# tree2023.net
KiCad netlist of a schematic drawn in EAGLE
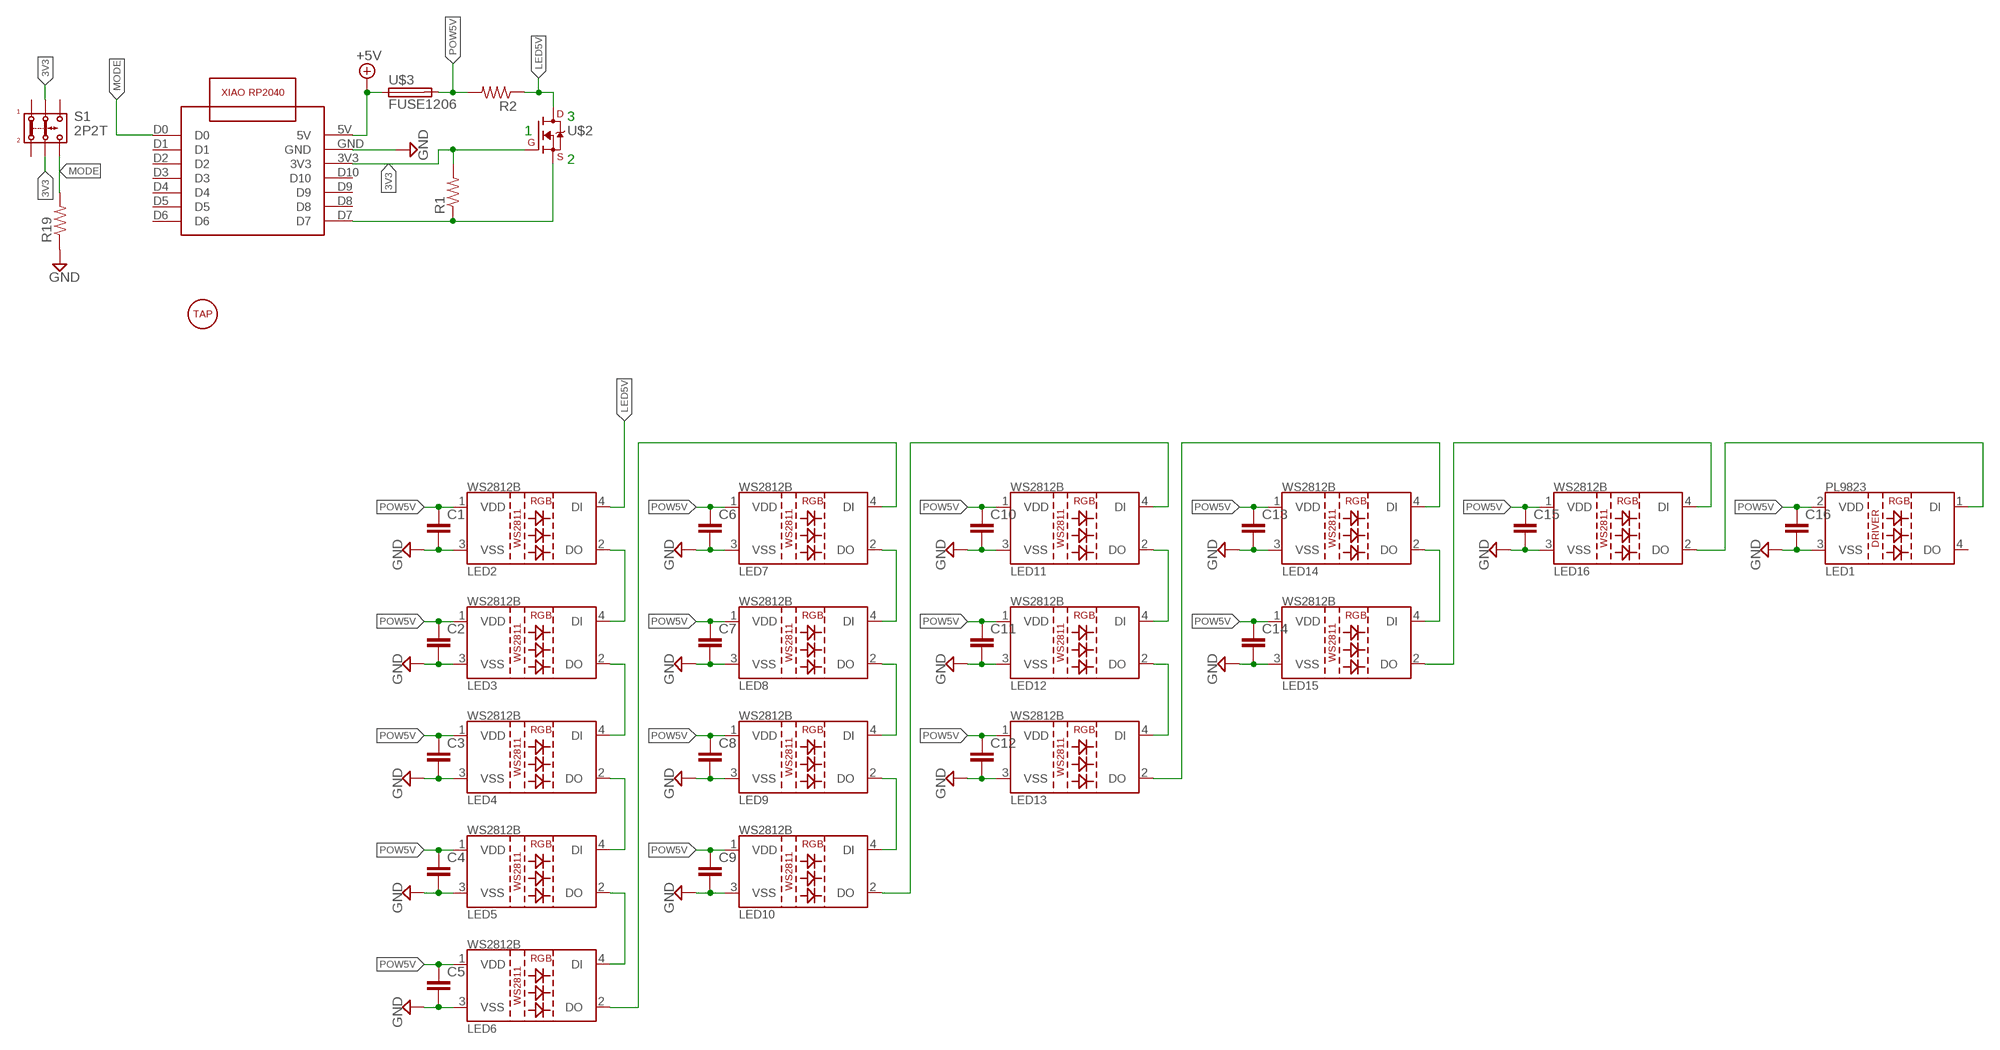
[diagram p0: schematic, sheet 1]

(export (version "E")
  (design (tool "Eeschema 10.0.6"))
  (components
    (comp (ref "C1")
      (value "C-EUC0805")
      (footprint "eagle-import:C0805")
      (libsource (lib "eagle-import") (part "C-EUC0805"))
    )
    (comp (ref "C2")
      (value "C-EUC0805")
      (footprint "eagle-import:C0805")
      (libsource (lib "eagle-import") (part "C-EUC0805"))
    )
    (comp (ref "C3")
      (value "C-EUC0805")
      (footprint "eagle-import:C0805")
      (libsource (lib "eagle-import") (part "C-EUC0805"))
    )
    (comp (ref "C4")
      (value "C-EUC0805")
      (footprint "eagle-import:C0805")
      (libsource (lib "eagle-import") (part "C-EUC0805"))
    )
    (comp (ref "C5")
      (value "C-EUC0805")
      (footprint "eagle-import:C0805")
      (libsource (lib "eagle-import") (part "C-EUC0805"))
    )
    (comp (ref "C6")
      (value "C-EUC0805")
      (footprint "eagle-import:C0805")
      (libsource (lib "eagle-import") (part "C-EUC0805"))
    )
    (comp (ref "C7")
      (value "C-EUC0805")
      (footprint "eagle-import:C0805")
      (libsource (lib "eagle-import") (part "C-EUC0805"))
    )
    (comp (ref "C8")
      (value "C-EUC0805")
      (footprint "eagle-import:C0805")
      (libsource (lib "eagle-import") (part "C-EUC0805"))
    )
    (comp (ref "C9")
      (value "C-EUC0805")
      (footprint "eagle-import:C0805")
      (libsource (lib "eagle-import") (part "C-EUC0805"))
    )
    (comp (ref "C10")
      (value "C-EUC0805")
      (footprint "eagle-import:C0805")
      (libsource (lib "eagle-import") (part "C-EUC0805"))
    )
    (comp (ref "C11")
      (value "C-EUC0805")
      (footprint "eagle-import:C0805")
      (libsource (lib "eagle-import") (part "C-EUC0805"))
    )
    (comp (ref "C12")
      (value "C-EUC0805")
      (footprint "eagle-import:C0805")
      (libsource (lib "eagle-import") (part "C-EUC0805"))
    )
    (comp (ref "C13")
      (value "C-EUC0805")
      (footprint "eagle-import:C0805")
      (libsource (lib "eagle-import") (part "C-EUC0805"))
    )
    (comp (ref "C14")
      (value "C-EUC0805")
      (footprint "eagle-import:C0805")
      (libsource (lib "eagle-import") (part "C-EUC0805"))
    )
    (comp (ref "C15")
      (value "C-EUC0805")
      (footprint "eagle-import:C0805")
      (libsource (lib "eagle-import") (part "C-EUC0805"))
    )
    (comp (ref "C16")
      (value "C-EUC0805")
      (footprint "eagle-import:C0805")
      (libsource (lib "eagle-import") (part "C-EUC0805"))
    )
    (comp (ref "LED1")
      (value "LED-PL9823-F5")
      (footprint "eagle-import:LED-PL9823-F5")
      (libsource (lib "eagle-import") (part "LED-PL9823-F5"))
    )
    (comp (ref "LED2")
      (value "LED-WS2812B")
      (footprint "eagle-import:LED-WS2812B")
      (libsource (lib "eagle-import") (part "LED-WS2812B"))
    )
    (comp (ref "LED3")
      (value "LED-WS2812B")
      (footprint "eagle-import:LED-WS2812B")
      (libsource (lib "eagle-import") (part "LED-WS2812B"))
    )
    (comp (ref "LED4")
      (value "LED-WS2812B")
      (footprint "eagle-import:LED-WS2812B")
      (libsource (lib "eagle-import") (part "LED-WS2812B"))
    )
    (comp (ref "LED5")
      (value "LED-WS2812B")
      (footprint "eagle-import:LED-WS2812B")
      (libsource (lib "eagle-import") (part "LED-WS2812B"))
    )
    (comp (ref "LED6")
      (value "LED-WS2812B")
      (footprint "eagle-import:LED-WS2812B")
      (libsource (lib "eagle-import") (part "LED-WS2812B"))
    )
    (comp (ref "LED7")
      (value "LED-WS2812B")
      (footprint "eagle-import:LED-WS2812B")
      (libsource (lib "eagle-import") (part "LED-WS2812B"))
    )
    (comp (ref "LED8")
      (value "LED-WS2812B")
      (footprint "eagle-import:LED-WS2812B")
      (libsource (lib "eagle-import") (part "LED-WS2812B"))
    )
    (comp (ref "LED9")
      (value "LED-WS2812B")
      (footprint "eagle-import:LED-WS2812B")
      (libsource (lib "eagle-import") (part "LED-WS2812B"))
    )
    (comp (ref "LED10")
      (value "LED-WS2812B")
      (footprint "eagle-import:LED-WS2812B")
      (libsource (lib "eagle-import") (part "LED-WS2812B"))
    )
    (comp (ref "LED11")
      (value "LED-WS2812B")
      (footprint "eagle-import:LED-WS2812B")
      (libsource (lib "eagle-import") (part "LED-WS2812B"))
    )
    (comp (ref "LED12")
      (value "LED-WS2812B")
      (footprint "eagle-import:LED-WS2812B")
      (libsource (lib "eagle-import") (part "LED-WS2812B"))
    )
    (comp (ref "LED13")
      (value "LED-WS2812B")
      (footprint "eagle-import:LED-WS2812B")
      (libsource (lib "eagle-import") (part "LED-WS2812B"))
    )
    (comp (ref "LED14")
      (value "LED-WS2812B")
      (footprint "eagle-import:LED-WS2812B")
      (libsource (lib "eagle-import") (part "LED-WS2812B"))
    )
    (comp (ref "LED15")
      (value "LED-WS2812B")
      (footprint "eagle-import:LED-WS2812B")
      (libsource (lib "eagle-import") (part "LED-WS2812B"))
    )
    (comp (ref "LED16")
      (value "LED-WS2812B")
      (footprint "eagle-import:LED-WS2812B")
      (libsource (lib "eagle-import") (part "LED-WS2812B"))
    )
    (comp (ref "R1")
      (value "R-US_R0603")
      (footprint "eagle-import:R0603")
      (libsource (lib "eagle-import") (part "R-US_R0603"))
    )
    (comp (ref "R2")
      (value "R-US_R0603")
      (footprint "eagle-import:R0603")
      (libsource (lib "eagle-import") (part "R-US_R0603"))
    )
    (comp (ref "R19")
      (value "R-US_R0603")
      (footprint "eagle-import:R0603")
      (libsource (lib "eagle-import") (part "R-US_R0603"))
    )
    (comp (ref "S1")
      (value "2P2T")
      (footprint "eagle-import:2P2T")
      (libsource (lib "eagle-import") (part "2P2T"))
    )
    (comp (ref "U$1")
      (value "XIAO-RP2040FRONT-SMD")
      (footprint "eagle-import:XIAO-RP2040-ASIDE-SMD")
      (libsource (lib "eagle-import") (part "XIAO-RP2040FRONT-SMD"))
    )
    (comp (ref "U$2")
      (value "IRML6344")
      (footprint "eagle-import:SOT23")
      (libsource (lib "eagle-import") (part "IRML6344"))
    )
    (comp (ref "U$3")
      (value "FUSE1206")
      (footprint "eagle-import:F1206")
      (libsource (lib "eagle-import") (part "FUSE1206"))
    )
    (comp (ref "U$4")
      (value "TAPHOLE3MM")
      (footprint "eagle-import:TAPHOLE-3MM")
      (libsource (lib "eagle-import") (part "TAPHOLE3MM"))
    )
  )
  (nets
    (net (code "1") (name "+5V") (class "Default")
      (node (ref "U$1") (pin "5V") (pinfunction "5V_5V") (pintype "bidirectional"))
      (node (ref "U$3") (pin "1") (pinfunction "1_1") (pintype "passive"))
    )
    (net (code "2") (name "3V3") (class "Default")
      (node (ref "R1") (pin "2") (pinfunction "2_2") (pintype "passive"))
      (node (ref "S1") (pin "2.1") (pinfunction "2.1_2.1") (pintype "passive"))
      (node (ref "S1") (pin "2.2") (pinfunction "2.2_2.2") (pintype "passive"))
      (node (ref "U$1") (pin "3V3") (pinfunction "3V3_3V3") (pintype "bidirectional"))
      (node (ref "U$2") (pin "1") (pinfunction "G_1") (pintype "passive"))
    )
    (net (code "3") (name "GND") (class "Default")
      (node (ref "C1") (pin "2") (pinfunction "2_2") (pintype "passive"))
      (node (ref "C10") (pin "2") (pinfunction "2_2") (pintype "passive"))
      (node (ref "C11") (pin "2") (pinfunction "2_2") (pintype "passive"))
      (node (ref "C12") (pin "2") (pinfunction "2_2") (pintype "passive"))
      (node (ref "C13") (pin "2") (pinfunction "2_2") (pintype "passive"))
      (node (ref "C14") (pin "2") (pinfunction "2_2") (pintype "passive"))
      (node (ref "C15") (pin "2") (pinfunction "2_2") (pintype "passive"))
      (node (ref "C16") (pin "2") (pinfunction "2_2") (pintype "passive"))
      (node (ref "C2") (pin "2") (pinfunction "2_2") (pintype "passive"))
      (node (ref "C3") (pin "2") (pinfunction "2_2") (pintype "passive"))
      (node (ref "C4") (pin "2") (pinfunction "2_2") (pintype "passive"))
      (node (ref "C5") (pin "2") (pinfunction "2_2") (pintype "passive"))
      (node (ref "C6") (pin "2") (pinfunction "2_2") (pintype "passive"))
      (node (ref "C7") (pin "2") (pinfunction "2_2") (pintype "passive"))
      (node (ref "C8") (pin "2") (pinfunction "2_2") (pintype "passive"))
      (node (ref "C9") (pin "2") (pinfunction "2_2") (pintype "passive"))
      (node (ref "LED1") (pin "3") (pinfunction "VSS_3") (pintype "bidirectional"))
      (node (ref "LED10") (pin "3") (pinfunction "VSS_3") (pintype "bidirectional"))
      (node (ref "LED11") (pin "3") (pinfunction "VSS_3") (pintype "bidirectional"))
      (node (ref "LED12") (pin "3") (pinfunction "VSS_3") (pintype "bidirectional"))
      (node (ref "LED13") (pin "3") (pinfunction "VSS_3") (pintype "bidirectional"))
      (node (ref "LED14") (pin "3") (pinfunction "VSS_3") (pintype "bidirectional"))
      (node (ref "LED15") (pin "3") (pinfunction "VSS_3") (pintype "bidirectional"))
      (node (ref "LED16") (pin "3") (pinfunction "VSS_3") (pintype "bidirectional"))
      (node (ref "LED2") (pin "3") (pinfunction "VSS_3") (pintype "bidirectional"))
      (node (ref "LED3") (pin "3") (pinfunction "VSS_3") (pintype "bidirectional"))
      (node (ref "LED4") (pin "3") (pinfunction "VSS_3") (pintype "bidirectional"))
      (node (ref "LED5") (pin "3") (pinfunction "VSS_3") (pintype "bidirectional"))
      (node (ref "LED6") (pin "3") (pinfunction "VSS_3") (pintype "bidirectional"))
      (node (ref "LED7") (pin "3") (pinfunction "VSS_3") (pintype "bidirectional"))
      (node (ref "LED8") (pin "3") (pinfunction "VSS_3") (pintype "bidirectional"))
      (node (ref "LED9") (pin "3") (pinfunction "VSS_3") (pintype "bidirectional"))
      (node (ref "R19") (pin "1") (pinfunction "1_1") (pintype "passive"))
      (node (ref "U$1") (pin "GND") (pinfunction "GND_GND") (pintype "bidirectional"))
    )
    (net (code "4") (name "LED5V") (class "Default")
      (node (ref "LED2") (pin "4") (pinfunction "DI_4") (pintype "bidirectional"))
      (node (ref "R2") (pin "1") (pinfunction "1_1") (pintype "passive"))
      (node (ref "U$2") (pin "3") (pinfunction "D_3") (pintype "passive"))
    )
    (net (code "5") (name "MODE") (class "Default")
      (node (ref "R19") (pin "2") (pinfunction "2_2") (pintype "passive"))
      (node (ref "S1") (pin "3.2") (pinfunction "3.2_3.2") (pintype "passive"))
      (node (ref "U$1") (pin "D0") (pinfunction "D0_D0") (pintype "bidirectional"))
    )
    (net (code "6") (name "Net-(LED1-DI)") (class "Default")
      (node (ref "LED1") (pin "1") (pinfunction "DI_1") (pintype "bidirectional"))
      (node (ref "LED16") (pin "2") (pinfunction "DO_2") (pintype "bidirectional"))
    )
    (net (code "7") (name "Net-(LED2-DO)") (class "Default")
      (node (ref "LED2") (pin "2") (pinfunction "DO_2") (pintype "bidirectional"))
      (node (ref "LED3") (pin "4") (pinfunction "DI_4") (pintype "bidirectional"))
    )
    (net (code "8") (name "Net-(LED3-DO)") (class "Default")
      (node (ref "LED3") (pin "2") (pinfunction "DO_2") (pintype "bidirectional"))
      (node (ref "LED4") (pin "4") (pinfunction "DI_4") (pintype "bidirectional"))
    )
    (net (code "9") (name "Net-(LED4-DO)") (class "Default")
      (node (ref "LED4") (pin "2") (pinfunction "DO_2") (pintype "bidirectional"))
      (node (ref "LED5") (pin "4") (pinfunction "DI_4") (pintype "bidirectional"))
    )
    (net (code "10") (name "Net-(LED5-DO)") (class "Default")
      (node (ref "LED5") (pin "2") (pinfunction "DO_2") (pintype "bidirectional"))
      (node (ref "LED6") (pin "4") (pinfunction "DI_4") (pintype "bidirectional"))
    )
    (net (code "11") (name "Net-(LED6-DO)") (class "Default")
      (node (ref "LED6") (pin "2") (pinfunction "DO_2") (pintype "bidirectional"))
      (node (ref "LED7") (pin "4") (pinfunction "DI_4") (pintype "bidirectional"))
    )
    (net (code "12") (name "Net-(LED7-DO)") (class "Default")
      (node (ref "LED7") (pin "2") (pinfunction "DO_2") (pintype "bidirectional"))
      (node (ref "LED8") (pin "4") (pinfunction "DI_4") (pintype "bidirectional"))
    )
    (net (code "13") (name "Net-(LED8-DO)") (class "Default")
      (node (ref "LED8") (pin "2") (pinfunction "DO_2") (pintype "bidirectional"))
      (node (ref "LED9") (pin "4") (pinfunction "DI_4") (pintype "bidirectional"))
    )
    (net (code "14") (name "Net-(LED10-DI)") (class "Default")
      (node (ref "LED10") (pin "4") (pinfunction "DI_4") (pintype "bidirectional"))
      (node (ref "LED9") (pin "2") (pinfunction "DO_2") (pintype "bidirectional"))
    )
    (net (code "15") (name "Net-(LED10-DO)") (class "Default")
      (node (ref "LED10") (pin "2") (pinfunction "DO_2") (pintype "bidirectional"))
      (node (ref "LED11") (pin "4") (pinfunction "DI_4") (pintype "bidirectional"))
    )
    (net (code "16") (name "Net-(LED11-DO)") (class "Default")
      (node (ref "LED11") (pin "2") (pinfunction "DO_2") (pintype "bidirectional"))
      (node (ref "LED12") (pin "4") (pinfunction "DI_4") (pintype "bidirectional"))
    )
    (net (code "17") (name "Net-(LED12-DO)") (class "Default")
      (node (ref "LED12") (pin "2") (pinfunction "DO_2") (pintype "bidirectional"))
      (node (ref "LED13") (pin "4") (pinfunction "DI_4") (pintype "bidirectional"))
    )
    (net (code "18") (name "Net-(LED13-DO)") (class "Default")
      (node (ref "LED13") (pin "2") (pinfunction "DO_2") (pintype "bidirectional"))
      (node (ref "LED14") (pin "4") (pinfunction "DI_4") (pintype "bidirectional"))
    )
    (net (code "19") (name "Net-(LED14-DO)") (class "Default")
      (node (ref "LED14") (pin "2") (pinfunction "DO_2") (pintype "bidirectional"))
      (node (ref "LED15") (pin "4") (pinfunction "DI_4") (pintype "bidirectional"))
    )
    (net (code "20") (name "Net-(LED15-DO)") (class "Default")
      (node (ref "LED15") (pin "2") (pinfunction "DO_2") (pintype "bidirectional"))
      (node (ref "LED16") (pin "4") (pinfunction "DI_4") (pintype "bidirectional"))
    )
    (net (code "21") (name "Net-(U$2-S)") (class "Default")
      (node (ref "R1") (pin "1") (pinfunction "1_1") (pintype "passive"))
      (node (ref "U$1") (pin "D7") (pinfunction "D7_D7") (pintype "bidirectional"))
      (node (ref "U$2") (pin "2") (pinfunction "S_2") (pintype "passive"))
    )
    (net (code "22") (name "POW5V") (class "Default")
      (node (ref "C1") (pin "1") (pinfunction "1_1") (pintype "passive"))
      (node (ref "C10") (pin "1") (pinfunction "1_1") (pintype "passive"))
      (node (ref "C11") (pin "1") (pinfunction "1_1") (pintype "passive"))
      (node (ref "C12") (pin "1") (pinfunction "1_1") (pintype "passive"))
      (node (ref "C13") (pin "1") (pinfunction "1_1") (pintype "passive"))
      (node (ref "C14") (pin "1") (pinfunction "1_1") (pintype "passive"))
      (node (ref "C15") (pin "1") (pinfunction "1_1") (pintype "passive"))
      (node (ref "C16") (pin "1") (pinfunction "1_1") (pintype "passive"))
      (node (ref "C2") (pin "1") (pinfunction "1_1") (pintype "passive"))
      (node (ref "C3") (pin "1") (pinfunction "1_1") (pintype "passive"))
      (node (ref "C4") (pin "1") (pinfunction "1_1") (pintype "passive"))
      (node (ref "C5") (pin "1") (pinfunction "1_1") (pintype "passive"))
      (node (ref "C6") (pin "1") (pinfunction "1_1") (pintype "passive"))
      (node (ref "C7") (pin "1") (pinfunction "1_1") (pintype "passive"))
      (node (ref "C8") (pin "1") (pinfunction "1_1") (pintype "passive"))
      (node (ref "C9") (pin "1") (pinfunction "1_1") (pintype "passive"))
      (node (ref "LED1") (pin "2") (pinfunction "VDD_2") (pintype "bidirectional"))
      (node (ref "LED10") (pin "1") (pinfunction "VDD_1") (pintype "bidirectional"))
      (node (ref "LED11") (pin "1") (pinfunction "VDD_1") (pintype "bidirectional"))
      (node (ref "LED12") (pin "1") (pinfunction "VDD_1") (pintype "bidirectional"))
      (node (ref "LED13") (pin "1") (pinfunction "VDD_1") (pintype "bidirectional"))
      (node (ref "LED14") (pin "1") (pinfunction "VDD_1") (pintype "bidirectional"))
      (node (ref "LED15") (pin "1") (pinfunction "VDD_1") (pintype "bidirectional"))
      (node (ref "LED16") (pin "1") (pinfunction "VDD_1") (pintype "bidirectional"))
      (node (ref "LED2") (pin "1") (pinfunction "VDD_1") (pintype "bidirectional"))
      (node (ref "LED3") (pin "1") (pinfunction "VDD_1") (pintype "bidirectional"))
      (node (ref "LED4") (pin "1") (pinfunction "VDD_1") (pintype "bidirectional"))
      (node (ref "LED5") (pin "1") (pinfunction "VDD_1") (pintype "bidirectional"))
      (node (ref "LED6") (pin "1") (pinfunction "VDD_1") (pintype "bidirectional"))
      (node (ref "LED7") (pin "1") (pinfunction "VDD_1") (pintype "bidirectional"))
      (node (ref "LED8") (pin "1") (pinfunction "VDD_1") (pintype "bidirectional"))
      (node (ref "LED9") (pin "1") (pinfunction "VDD_1") (pintype "bidirectional"))
      (node (ref "R2") (pin "2") (pinfunction "2_2") (pintype "passive"))
      (node (ref "U$3") (pin "2") (pinfunction "2_2") (pintype "passive"))
    )
    (net (code "23") (name "unconnected-(LED1-DO-Pad4)") (class "Default")
      (node (ref "LED1") (pin "4") (pinfunction "DO_4") (pintype "bidirectional"))
    )
    (net (code "24") (name "unconnected-(S1-Pad1.1)") (class "Default")
      (node (ref "S1") (pin "1.1") (pinfunction "1.1_1.1") (pintype "passive"))
    )
    (net (code "25") (name "unconnected-(S1-Pad1.2)") (class "Default")
      (node (ref "S1") (pin "1.2") (pinfunction "1.2_1.2") (pintype "passive"))
    )
    (net (code "26") (name "unconnected-(S1-Pad3.1)") (class "Default")
      (node (ref "S1") (pin "3.1") (pinfunction "3.1_3.1") (pintype "passive"))
    )
    (net (code "27") (name "unconnected-(U$1-PadD1)") (class "Default")
      (node (ref "U$1") (pin "D1") (pinfunction "D1_D1") (pintype "bidirectional"))
    )
    (net (code "28") (name "unconnected-(U$1-PadD2)") (class "Default")
      (node (ref "U$1") (pin "D2") (pinfunction "D2_D2") (pintype "bidirectional"))
    )
    (net (code "29") (name "unconnected-(U$1-PadD3)") (class "Default")
      (node (ref "U$1") (pin "D3") (pinfunction "D3_D3") (pintype "bidirectional"))
    )
    (net (code "30") (name "unconnected-(U$1-PadD4)") (class "Default")
      (node (ref "U$1") (pin "D4") (pinfunction "D4_D4") (pintype "bidirectional"))
    )
    (net (code "31") (name "unconnected-(U$1-PadD5)") (class "Default")
      (node (ref "U$1") (pin "D5") (pinfunction "D5_D5") (pintype "bidirectional"))
    )
    (net (code "32") (name "unconnected-(U$1-PadD6)") (class "Default")
      (node (ref "U$1") (pin "D6") (pinfunction "D6_D6") (pintype "bidirectional"))
    )
    (net (code "33") (name "unconnected-(U$1-PadD8)") (class "Default")
      (node (ref "U$1") (pin "D8") (pinfunction "D8_D8") (pintype "bidirectional"))
    )
    (net (code "34") (name "unconnected-(U$1-PadD9)") (class "Default")
      (node (ref "U$1") (pin "D9") (pinfunction "D9_D9") (pintype "bidirectional"))
    )
    (net (code "35") (name "unconnected-(U$1-PadD10)") (class "Default")
      (node (ref "U$1") (pin "D10") (pinfunction "D10_D10") (pintype "bidirectional"))
    )
  )
)
